# Sheet1.net
KiCad netlist of a schematic drawn in Altium Designer
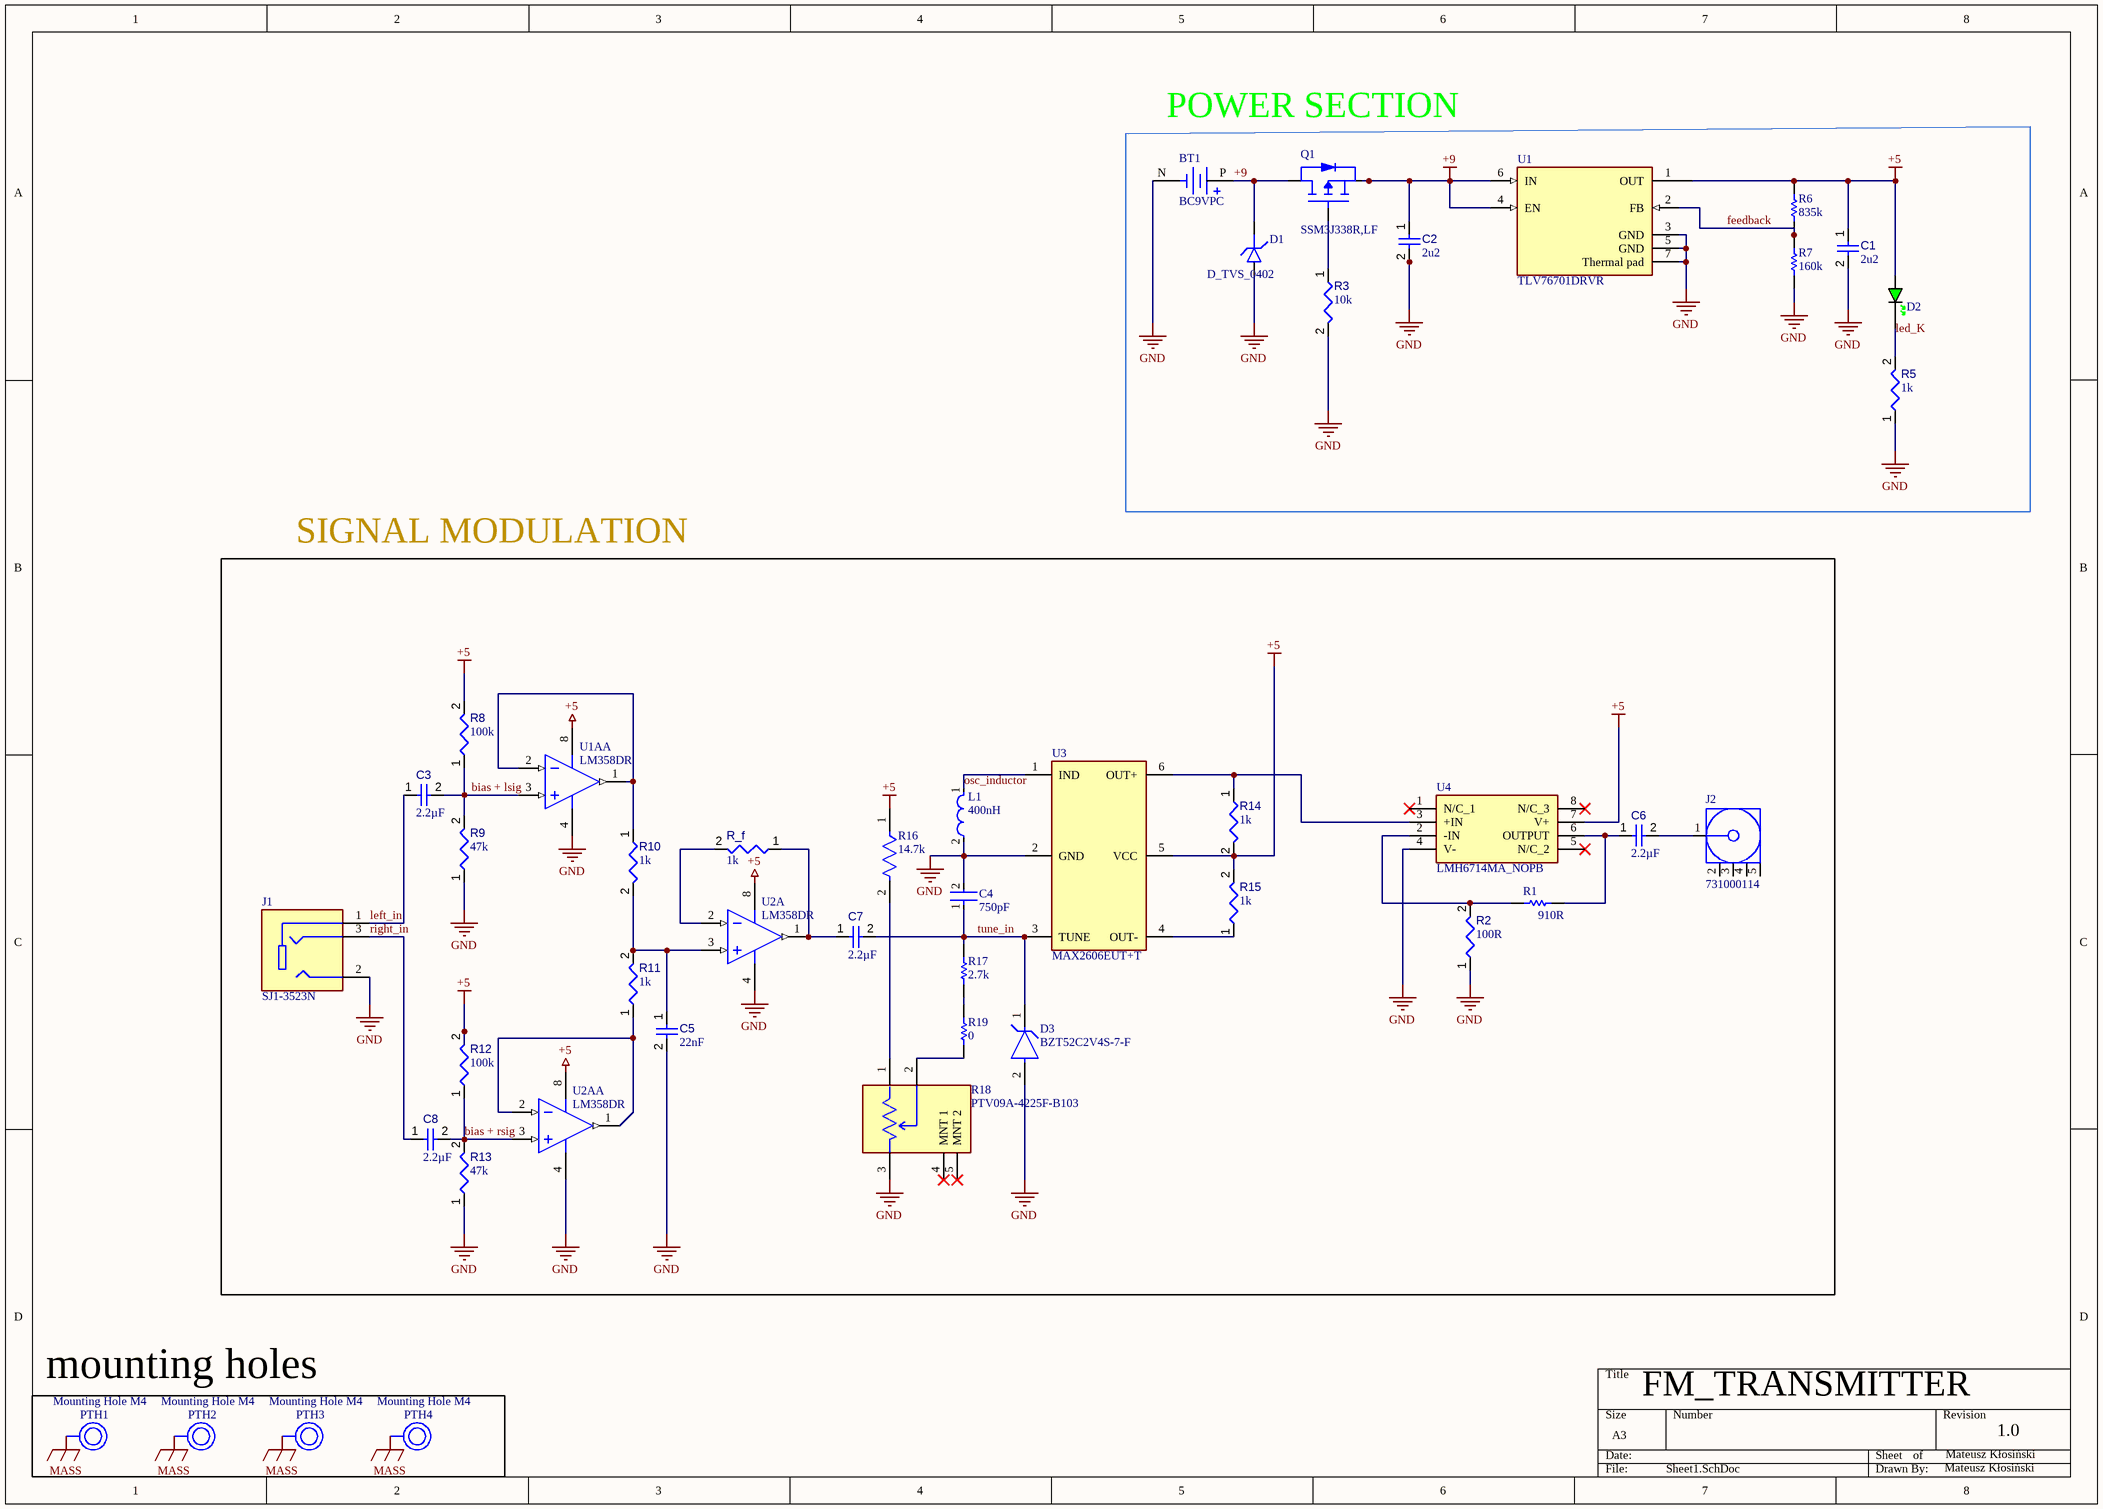
[diagram p0: Sheet1.SchDoc]

(export (version "E")
  (design (tool "Eeschema 10.0.6"))
  (components
    (comp (ref "BT1")
      (value "BC9VPC")
      (footprint "BAT_BC9VPC")
      (description "Battery Holder 1 Cells 9V Size Plastic Tray")
      (fields (field (name "MF") "MPD (Memory Protection Devices)"))
      (libsource (lib "PWr in Space team") (part "BC9VPC"))
    )
    (comp (ref "C1")
      (value "2u2")
      (footprint "CAPC0805(2012)145_L")
      (description "Chip Capacitor, 100µF +/-20%, 6.3V, 0805, Thickness 1.45 mm")
      (fields (field (name "TOLERANCE") "10%") (field (name "Comment") "Capacitor 100µF +/-20% 6.3V 0805"))
      (libsource (lib "PWr in Space team") (part "CAP-NP-2"))
    )
    (comp (ref "C2")
      (value "2u2")
      (footprint "CAPC0805(2012)145_L")
      (description "Chip Capacitor, 100µF +/-20%, 6.3V, 0805, Thickness 1.45 mm")
      (fields (field (name "TOLERANCE") "10%") (field (name "Comment") "Capacitor 100µF +/-20% 6.3V 0805"))
      (libsource (lib "PWr in Space team") (part "CAP-NP-2"))
    )
    (comp (ref "C3")
      (value "2.2µF")
      (footprint "CAPC0402(1005)60_L")
      (description "Chip Capacitor, 2,2µF +/-20%, 10V, 0402, Thickness 0.6 mm")
      (fields (field (name "TOLERANCE") "10%") (field (name "Comment") "Capacitor 2,2µF +/-20% 10V 0402"))
      (libsource (lib "PWr in Space team") (part "CAP-NP-2"))
    )
    (comp (ref "C4")
      (value "750pF")
      (footprint "FP-C0402-BB-MFG")
      (description "CAP CER 750PF 50V NP0 0402")
      (fields
        (field (name "MANUFACTURER") "Kemet")
        (field (name "OCTOPART") "https://octopart.com/c0402c751j5gactu-kemet-19049839")
      )
      (libsource (lib "Altium Content Vault") (part "b4654b650e69147ec39a6b967a45e02"))
    )
    (comp (ref "C5")
      (value "22nF")
      (footprint "CAPC0402(1005)60_L")
      (description "Chip Capacitor, 22nF +/-20%, 10V, 0402, Thickness 0.6 mm")
      (fields (field (name "TOLERANCE") "10%") (field (name "Comment") "Capacitor 22nF +/-20% 10V 0402"))
      (libsource (lib "PWr in Space team") (part "CAP-NP-2"))
    )
    (comp (ref "C6")
      (value "2.2µF")
      (footprint "CAPC0402(1005)60_L")
      (description "Chip Capacitor, 2,2µF +/-20%, 10V, 0402, Thickness 0.6 mm")
      (fields (field (name "TOLERANCE") "10%") (field (name "Comment") "Capacitor 2,2µF +/-20% 10V 0402"))
      (libsource (lib "PWr in Space team") (part "CAP-NP-2"))
    )
    (comp (ref "C7")
      (value "2.2µF")
      (footprint "CAPC0402(1005)60_L")
      (description "Chip Capacitor, 2,2µF +/-20%, 10V, 0402, Thickness 0.6 mm")
      (fields (field (name "TOLERANCE") "10%") (field (name "Comment") "Capacitor 2,2µF +/-20% 10V 0402"))
      (libsource (lib "PWr in Space team") (part "CAP-NP-2"))
    )
    (comp (ref "C8")
      (value "2.2µF")
      (footprint "CAPC0402(1005)60_L")
      (description "Chip Capacitor, 2,2µF +/-20%, 10V, 0402, Thickness 0.6 mm")
      (fields (field (name "TOLERANCE") "10%") (field (name "Comment") "Capacitor 2,2µF +/-20% 10V 0402"))
      (libsource (lib "PWr in Space team") (part "CAP-NP-2"))
    )
    (comp (ref "D1")
      (value "D_TVS_0402")
      (footprint "D_0402")
      (description "Diode TVS / ESD 0402")
      (libsource (lib "Schematic-Lib-PhilsLab") (part "D_TVS_0402"))
    )
    (comp (ref "D2")
      (value "GREEN")
      (footprint "LED_0805_GREEN")
      (description "LED 0805 GREEN SMD")
      (libsource (lib "Schematic-Lib-PhilsLab") (part "LED_0805_GREEN"))
    )
    (comp (ref "D3")
      (value "BZT52C2V4S-7-F")
      (footprint "FP-SOD323-IPC_B")
      (description "DIODE ZENER 2.4V 200MW SOD323")
      (fields (field (name "TOLERANCE") "8%"))
      (libsource (lib "Altium Content Vault") (part "f813f71cba58e380607f5dd3caf9714"))
    )
    (comp (ref "J1")
      (value "SJ1-3523N")
      (footprint "CUI_SJ1-3523N")
      (description "3.5 mm, Stereo, Right Angle, Through Hole, 3 Conductors, 0 Internal Switches, Audio Jack Connector")
      (fields (field (name "MF") "CUI Devices"))
      (libsource (lib "PWr in Space team") (part "SJ1-3523N"))
    )
    (comp (ref "J2")
      (value "731000114")
      (footprint "MOLX-731000114_V")
      (description "SMA Right-Angle PCB Jack Receptacle, Brass Body, Gold Plated, 50 Ohm, 5-Pin THD, RoHS, Tray")
      (fields (field (name "MANUFACTURER") "Molex"))
      (libsource (lib "Altium Content Vault") (part "CN-S-4F-RF5"))
    )
    (comp (ref "L1")
      (value "400nH")
      (footprint "FP-LQW18CA_00-MFG")
      (description "Wire Wound Ferrite type RF Inductor 400nH ±5% 680mA 0.26Ω 0603 (1608)")
      (libsource (lib "Altium Content Vault") (part "725321dda6339637d4d059423bc1c3c"))
    )
    (comp (ref "PTH1")
      (value "Mounting Hole M4")
      (footprint "Mounting Hole M4")
      (description "M4 size screw hole")
      (libsource (lib "PWr in Space team") (part "Mounting Hole M4"))
    )
    (comp (ref "PTH2")
      (value "Mounting Hole M4")
      (footprint "Mounting Hole M4")
      (description "M4 size screw hole")
      (libsource (lib "PWr in Space team") (part "Mounting Hole M4"))
    )
    (comp (ref "PTH3")
      (value "Mounting Hole M4")
      (footprint "Mounting Hole M4")
      (description "M4 size screw hole")
      (libsource (lib "PWr in Space team") (part "Mounting Hole M4"))
    )
    (comp (ref "PTH4")
      (value "Mounting Hole M4")
      (footprint "Mounting Hole M4")
      (description "M4 size screw hole")
      (libsource (lib "PWr in Space team") (part "Mounting Hole M4"))
    )
    (comp (ref "Q1")
      (value "SSM3J338R,LF")
      (footprint "SSM3J338R,LF-SOT23-F")
      (description "MOSFET P-Channel Vds=12V Id=6A")
      (fields (field (name "MANUFACTURER PART NUMBER") "Toshiba"))
      (libsource (lib "Schematic-Lib-PhilsLab") (part "SSM3J338R,LF"))
    )
    (comp (ref "R1")
      (value "910R")
      (footprint "RESC1608X55X30NL15T15")
      (fields (field (name "MANUFACTURER") "Panasonic") (field (name "PART NUMBER") "ERJ-3EKF9100V"))
      (libsource (lib "Altium Content Vault") (part "RES"))
    )
    (comp (ref "R2")
      (value "100R")
      (footprint "RESC0402(1005)_L")
      (description "100R 0.063W 1% 0402 (1005 Metric)  SMD")
      (fields (field (name "TOLERANCE") "1%") (field (name "POWER") "63mW"))
      (libsource (lib "PWr in Space team") (part "100R2F"))
    )
    (comp (ref "R3")
      (value "10k")
      (footprint "RESC0402(1005)_L")
      (description "10K 0.063W 1% 0402 (1005 Metric)  SMD")
      (fields (field (name "POWER") "63mW") (field (name "TOLERANCE") "1%"))
      (libsource (lib "PWr in Space team") (part "10KR2F"))
    )
    (comp (ref "R5")
      (value "1k")
      (footprint "RESC0805(2012)_L")
      (description "1K 0.125W 5% 0805 (2012 Metric)  SMD")
      (fields (field (name "TOLERANCE") "5%") (field (name "POWER") "125mW"))
      (libsource (lib "PWr in Space team") (part "1KR5J"))
    )
    (comp (ref "R6")
      (value "Resistor 1k +/-1% 0805 125 mW")
      (footprint "RESC2013X70X40ML20T20")
      (description "Chip Resistor, 1 KOhm, +/- 1%, 0.125 W, -55 to 155 degC, 0805 (2013 Metric)")
      (fields (field (name "TOLERANCE") "1%") (field (name "POWER") "125mW") (field (name "840K") "835k"))
      (libsource (lib "") (part "RES-2_1"))
    )
    (comp (ref "R7")
      (value "160k")
      (footprint "RESC2013X70X40ML20T20")
      (description "Chip Resistor, 1 KOhm, +/- 1%, 0.125 W, -55 to 155 degC, 0805 (2013 Metric)")
      (fields (field (name "TOLERANCE") "1%") (field (name "POWER") "125mW"))
      (libsource (lib "") (part "RES-2_1"))
    )
    (comp (ref "R8")
      (value "100k")
      (footprint "RESC1608X55X25ML10T15")
      (description "Chip Resistor, 100 KOhm, +/- 1%, 0.1 W, -55 to 155 degC, 0603 (1608 Metric)")
      (fields (field (name "TOLERANCE") "1%") (field (name "POWER") "100mW"))
      (libsource (lib "PWr in Space team") (part "RES-2"))
    )
    (comp (ref "R9")
      (value "47k")
      (footprint "FP-ERA2A-IPC_B")
      (description "Fixed Resistor, Thin Film, 0.063W, 47000ohm, 50V, 0.1% +/-Tol, 25ppm/Cel, Surface Mount, 0402")
      (fields (field (name "TOLERANCE") "0.1%") (field (name "POWER") "63mW"))
      (libsource (lib "PWr in Space team") (part "RES-2"))
    )
    (comp (ref "R10")
      (value "1k")
      (footprint "RESC0805(2012)_L")
      (description "1K 0.125W 5% 0805 (2012 Metric)  SMD")
      (fields (field (name "TOLERANCE") "5%") (field (name "POWER") "125mW"))
      (libsource (lib "PWr in Space team") (part "1KR5J"))
    )
    (comp (ref "R11")
      (value "1k")
      (footprint "RESC0805(2012)_L")
      (description "1K 0.125W 5% 0805 (2012 Metric)  SMD")
      (fields (field (name "TOLERANCE") "5%") (field (name "POWER") "125mW"))
      (libsource (lib "PWr in Space team") (part "1KR5J"))
    )
    (comp (ref "R12")
      (value "100k")
      (footprint "RESC1608X55X25ML10T15")
      (description "Chip Resistor, 100 KOhm, +/- 1%, 0.1 W, -55 to 155 degC, 0603 (1608 Metric)")
      (fields (field (name "TOLERANCE") "1%") (field (name "POWER") "100mW"))
      (libsource (lib "PWr in Space team") (part "RES-2"))
    )
    (comp (ref "R13")
      (value "47k")
      (footprint "FP-ERA2A-IPC_B")
      (description "Fixed Resistor, Thin Film, 0.063W, 47000ohm, 50V, 0.1% +/-Tol, 25ppm/Cel, Surface Mount, 0402")
      (fields (field (name "TOLERANCE") "0.1%") (field (name "POWER") "63mW"))
      (libsource (lib "PWr in Space team") (part "RES-2"))
    )
    (comp (ref "R14")
      (value "1k")
      (footprint "RESC0805(2012)_L")
      (description "1K 0.125W 5% 0805 (2012 Metric)  SMD")
      (fields (field (name "TOLERANCE") "5%") (field (name "POWER") "125mW"))
      (libsource (lib "PWr in Space team") (part "1KR5J"))
    )
    (comp (ref "R15")
      (value "1k")
      (footprint "RESC0805(2012)_L")
      (description "1K 0.125W 5% 0805 (2012 Metric)  SMD")
      (fields (field (name "TOLERANCE") "5%") (field (name "POWER") "125mW"))
      (libsource (lib "PWr in Space team") (part "1KR5J"))
    )
    (comp (ref "R16")
      (value "14.7k")
      (footprint "FP-ERA3A-MFG")
      (description "RES SMD 14.7KOHM 0.1% 1/10W 0603")
      (fields
        (field (name "OCTOPART") "https://octopart.com/era3aeb1472v-panasonic-42876006")
        (field (name "TOLERANCE") "0.1%")
      )
      (libsource (lib "Altium Content Vault") (part "1029c3af85768c4190bb7ad29bc67b5"))
    )
    (comp (ref "R17")
      (value "2.7k")
      (footprint "RESC1608X55X30NL20T20")
      (fields (field (name "MANUFACTURER") "Panasonic") (field (name "PART NUMBER") "ERA3AEB272V"))
      (libsource (lib "Altium Content Vault") (part "RES"))
    )
    (comp (ref "R18")
      (value "PTV09A-4225F-B103")
      (footprint "FP-PTV09A-4-MFG")
      (description "POT 10K OHM 1/20W CARBON LINEAR")
      (fields (field (name "TOLERANCE") "20%"))
      (libsource (lib "Altium Content Vault") (part "705d11b747745a787204d796a5f3d12"))
    )
    (comp (ref "R19")
      (value "0")
      (footprint "RESC1005X40X25ML05T10")
      (description "Chip Resistor, 0 Ohm, 0.063 W, -55 to 155 degC, 0402 (1005 Metric)")
      (fields (field (name "POWER") "63mW") (field (name "Comment") "Resistor 0R 0402 63 mW"))
      (libsource (lib "") (part "RES-2_1"))
    )
    (comp (ref "R_f")
      (value "1k")
      (footprint "RESC0805(2012)_L")
      (description "1K 0.125W 5% 0805 (2012 Metric)  SMD")
      (fields (field (name "TOLERANCE") "5%") (field (name "POWER") "125mW"))
      (libsource (lib "PWr in Space team") (part "1KR5J"))
    )
    (comp (ref "U1")
      (value "TLV76701DRVR")
      (footprint "FP-DRV0006A-IPC_C")
      (description "IC REG LINEAR POS ADJ 1A 6WSON")
      (libsource (lib "Altium Content Vault") (part "02b25d0a349586096ecc9dc1ae98da2"))
    )
    (comp (ref "U1A")
      (value "LM358DR")
      (footprint "D0008A_L")
      (fields (field (name "MANUFACTURER") "Texas Instruments (TI)"))
      (libsource (lib "PWr in Space team") (part "TI-LM358-8"))
    )
    (comp (ref "U2")
      (value "LM358DR")
      (footprint "D0008A_L")
      (fields (field (name "MANUFACTURER") "Texas Instruments (TI)"))
      (libsource (lib "PWr in Space team") (part "TI-LM358-8"))
    )
    (comp (ref "U2A")
      (value "LM358DR")
      (footprint "D0008A_L")
      (fields (field (name "MANUFACTURER") "Texas Instruments (TI)"))
      (libsource (lib "PWr in Space team") (part "TI-LM358-8"))
    )
    (comp (ref "U3")
      (value "MAX2606EUT+T")
      (footprint "SOT95P280X145-6N")
      (description "VCO Oscillators 45MHz to 650MHz, Integrated IF VCOs with Differential Output")
      (fields (field (name "MOUSER PART NUMBER") "700-MAX2606EUTT"))
      (libsource (lib "MAX2606EUT+T") (part "MAX2606EUT+T"))
    )
    (comp (ref "U4")
      (value "LMH6714MA_NOPB")
      (footprint "SOIC127P600X175-8N")
      (description "Video op amp,LMH6714MA 250MHz  SO8")
      (fields
        (field (name "MOUSER PART NUMBER") "926-LMH6714MA/NOPB")
        (field (name "MANUFACTURER_PART_NUMBER") "LMH6714MA/NOPB")
      )
      (libsource (lib "LMH6714MA_NOPB") (part "LMH6714MA_NOPB"))
    )
  )
  (nets
    (net (code "1") (name "+5") (class "Default")
      (node (ref "C1") (pin "1") (pinfunction "1_1") (pintype "passive"))
      (node (ref "D2") (pin "A") (pinfunction "A_A") (pintype "passive"))
      (node (ref "R12") (pin "2") (pinfunction "2_2") (pintype "passive"))
      (node (ref "R14") (pin "2") (pinfunction "2_2") (pintype "passive"))
      (node (ref "R15") (pin "2") (pinfunction "2_2") (pintype "passive"))
      (node (ref "R16") (pin "1") (pinfunction "1_1") (pintype "passive"))
      (node (ref "R6") (pin "2") (pinfunction "2_2") (pintype "passive"))
      (node (ref "R8") (pin "2") (pinfunction "2_2") (pintype "passive"))
      (node (ref "U1") (pin "1") (pinfunction "OUT_1") (pintype "passive"))
      (node (ref "U1A") (pin "8") (pinfunction "VCC_8") (pintype "power_in"))
      (node (ref "U2") (pin "8") (pinfunction "VCC_8") (pintype "power_in"))
      (node (ref "U2A") (pin "8") (pinfunction "VCC_8") (pintype "power_in"))
      (node (ref "U3") (pin "5") (pinfunction "VCC_5") (pintype "passive"))
      (node (ref "U4") (pin "7") (pinfunction "V+_7") (pintype "passive"))
    )
    (net (code "2") (name "+9") (class "Default")
      (node (ref "BT1") (pin "P") (pinfunction "POS_P") (pintype "passive"))
      (node (ref "C2") (pin "1") (pinfunction "1_1") (pintype "passive"))
      (node (ref "D1") (pin "K") (pinfunction "K_K") (pintype "passive"))
      (node (ref "Q1") (pin "D") (pinfunction "D_D") (pintype "passive"))
      (node (ref "Q1") (pin "S") (pinfunction "S_S") (pintype "passive"))
      (node (ref "U1") (pin "4") (pinfunction "EN_4") (pintype "input"))
      (node (ref "U1") (pin "6") (pinfunction "IN_6") (pintype "input"))
    )
    (net (code "3") (name "/bias + lsig") (class "Default")
      (node (ref "C3") (pin "2") (pinfunction "2_2") (pintype "passive"))
      (node (ref "R8") (pin "1") (pinfunction "1_1") (pintype "passive"))
      (node (ref "R9") (pin "2") (pinfunction "2_2") (pintype "passive"))
      (node (ref "U1A") (pin "3") (pinfunction "1IN+_3") (pintype "input"))
    )
    (net (code "4") (name "/bias + rsig") (class "Default")
      (node (ref "C8") (pin "2") (pinfunction "2_2") (pintype "passive"))
      (node (ref "R12") (pin "1") (pinfunction "1_1") (pintype "passive"))
      (node (ref "R13") (pin "2") (pinfunction "2_2") (pintype "passive"))
      (node (ref "U2A") (pin "3") (pinfunction "1IN+_3") (pintype "input"))
    )
    (net (code "5") (name "/feedback") (class "Default")
      (node (ref "R6") (pin "1") (pinfunction "1_1") (pintype "passive"))
      (node (ref "R7") (pin "2") (pinfunction "2_2") (pintype "passive"))
      (node (ref "U1") (pin "2") (pinfunction "FB_2") (pintype "input"))
    )
    (net (code "6") (name "/led_K") (class "Default")
      (node (ref "D2") (pin "K") (pinfunction "K_K") (pintype "passive"))
      (node (ref "R5") (pin "2") (pinfunction "2_2") (pintype "passive"))
    )
    (net (code "7") (name "/left_in") (class "Default")
      (node (ref "C3") (pin "1") (pinfunction "1_1") (pintype "passive"))
      (node (ref "J1") (pin "1") (pinfunction "1_1") (pintype "passive"))
    )
    (net (code "8") (name "/osc_inductor") (class "Default")
      (node (ref "L1") (pin "1") (pinfunction "1_1") (pintype "passive"))
      (node (ref "U3") (pin "1") (pinfunction "IND_1") (pintype "passive"))
    )
    (net (code "9") (name "/right_in") (class "Default")
      (node (ref "C8") (pin "1") (pinfunction "1_1") (pintype "passive"))
      (node (ref "J1") (pin "3") (pinfunction "3_3") (pintype "passive"))
    )
    (net (code "10") (name "/tune_in") (class "Default")
      (node (ref "C4") (pin "1") (pinfunction "1_1") (pintype "passive"))
      (node (ref "C7") (pin "2") (pinfunction "2_2") (pintype "passive"))
      (node (ref "D3") (pin "1") (pinfunction "C_1") (pintype "passive"))
      (node (ref "R17") (pin "2") (pinfunction "2_2") (pintype "passive"))
      (node (ref "U3") (pin "3") (pinfunction "TUNE_3") (pintype "passive"))
    )
    (net (code "11") (name "GND") (class "Default")
      (node (ref "BT1") (pin "N") (pinfunction "NEG_N") (pintype "passive"))
      (node (ref "C1") (pin "2") (pinfunction "2_2") (pintype "passive"))
      (node (ref "C2") (pin "2") (pinfunction "2_2") (pintype "passive"))
      (node (ref "C4") (pin "2") (pinfunction "2_2") (pintype "passive"))
      (node (ref "C5") (pin "2") (pinfunction "2_2") (pintype "passive"))
      (node (ref "D1") (pin "A") (pinfunction "A_A") (pintype "passive"))
      (node (ref "D3") (pin "2") (pinfunction "A_2") (pintype "passive"))
      (node (ref "J1") (pin "2") (pinfunction "2_2") (pintype "passive"))
      (node (ref "L1") (pin "2") (pinfunction "2_2") (pintype "passive"))
      (node (ref "R13") (pin "1") (pinfunction "1_1") (pintype "passive"))
      (node (ref "R18") (pin "3") (pinfunction "3_3") (pintype "passive"))
      (node (ref "R2") (pin "1") (pinfunction "1_1") (pintype "passive"))
      (node (ref "R3") (pin "2") (pinfunction "2_2") (pintype "passive"))
      (node (ref "R5") (pin "1") (pinfunction "1_1") (pintype "passive"))
      (node (ref "R7") (pin "1") (pinfunction "1_1") (pintype "passive"))
      (node (ref "R9") (pin "1") (pinfunction "1_1") (pintype "passive"))
      (node (ref "U1") (pin "3") (pinfunction "GND_3") (pintype "power_in"))
      (node (ref "U1") (pin "5") (pinfunction "GND_5") (pintype "power_in"))
      (node (ref "U1") (pin "7") (pinfunction "Thermal_pad_7") (pintype "power_in"))
      (node (ref "U1A") (pin "4") (pinfunction "GND_4") (pintype "power_in"))
      (node (ref "U2") (pin "4") (pinfunction "GND_4") (pintype "power_in"))
      (node (ref "U2A") (pin "4") (pinfunction "GND_4") (pintype "power_in"))
      (node (ref "U3") (pin "2") (pinfunction "GND_2") (pintype "passive"))
      (node (ref "U4") (pin "4") (pinfunction "V-_4") (pintype "passive"))
    )
    (net (code "12") (name "MASS") (class "Default")
      (node (ref "PTH1") (pin "3") (pinfunction "3_3") (pintype "passive"))
      (node (ref "PTH2") (pin "3") (pinfunction "3_3") (pintype "passive"))
      (node (ref "PTH3") (pin "3") (pinfunction "3_3") (pintype "passive"))
      (node (ref "PTH4") (pin "3") (pinfunction "3_3") (pintype "passive"))
    )
    (net (code "13") (name "Net-(C6-Pad2)") (class "Default")
      (node (ref "C6") (pin "2") (pinfunction "2_2") (pintype "passive"))
      (node (ref "J2") (pin "1") (pinfunction "1_1") (pintype "passive"))
    )
    (net (code "14") (name "Net-(Q1-PadG)") (class "Default")
      (node (ref "Q1") (pin "G") (pinfunction "G_G") (pintype "passive"))
      (node (ref "R3") (pin "1") (pinfunction "1_1") (pintype "passive"))
    )
    (net (code "15") (name "Net-(R16-Pad2)") (class "Default")
      (node (ref "R16") (pin "2") (pinfunction "2_2") (pintype "passive"))
      (node (ref "R18") (pin "1") (pinfunction "1_1") (pintype "passive"))
    )
    (net (code "16") (name "Net-(R17-Pad1)") (class "Default")
      (node (ref "R17") (pin "1") (pinfunction "1_1") (pintype "passive"))
      (node (ref "R19") (pin "2") (pinfunction "2_2") (pintype "passive"))
    )
    (net (code "17") (name "Net-(R18-Pad2)") (class "Default")
      (node (ref "R18") (pin "2") (pinfunction "2_2") (pintype "passive"))
      (node (ref "R19") (pin "1") (pinfunction "1_1") (pintype "passive"))
    )
    (net (code "18") (name "Net-(U1AA-1IN-)") (class "Default")
      (node (ref "R10") (pin "1") (pinfunction "1_1") (pintype "passive"))
      (node (ref "U1A") (pin "1") (pinfunction "1OUT_1") (pintype "output"))
      (node (ref "U1A") (pin "2") (pinfunction "1IN-_2") (pintype "input"))
    )
    (net (code "19") (name "Net-(U2A-1IN+)") (class "Default")
      (node (ref "C5") (pin "1") (pinfunction "1_1") (pintype "passive"))
      (node (ref "R10") (pin "2") (pinfunction "2_2") (pintype "passive"))
      (node (ref "R11") (pin "2") (pinfunction "2_2") (pintype "passive"))
      (node (ref "U2") (pin "3") (pinfunction "1IN+_3") (pintype "input"))
    )
    (net (code "20") (name "Net-(U2A-1IN-)") (class "Default")
      (node (ref "R_f") (pin "2") (pinfunction "2_2") (pintype "passive"))
      (node (ref "U2") (pin "2") (pinfunction "1IN-_2") (pintype "input"))
    )
    (net (code "21") (name "Net-(U2A-1OUT)") (class "Default")
      (node (ref "C7") (pin "1") (pinfunction "1_1") (pintype "passive"))
      (node (ref "R_f") (pin "1") (pinfunction "1_1") (pintype "passive"))
      (node (ref "U2") (pin "1") (pinfunction "1OUT_1") (pintype "output"))
    )
    (net (code "22") (name "Net-(U2AA-1IN-)") (class "Default")
      (node (ref "R11") (pin "1") (pinfunction "1_1") (pintype "passive"))
      (node (ref "U2A") (pin "1") (pinfunction "1OUT_1") (pintype "output"))
      (node (ref "U2A") (pin "2") (pinfunction "1IN-_2") (pintype "input"))
    )
    (net (code "23") (name "Net-(U3-OUT+)") (class "Default")
      (node (ref "R14") (pin "1") (pinfunction "1_1") (pintype "passive"))
      (node (ref "U3") (pin "6") (pinfunction "OUT+_6") (pintype "passive"))
      (node (ref "U4") (pin "3") (pinfunction "+IN_3") (pintype "passive"))
    )
    (net (code "24") (name "Net-(U3-OUT-)") (class "Default")
      (node (ref "R15") (pin "1") (pinfunction "1_1") (pintype "passive"))
      (node (ref "U3") (pin "4") (pinfunction "OUT-_4") (pintype "passive"))
    )
    (net (code "25") (name "Net-(U4--IN)") (class "Default")
      (node (ref "R1") (pin "1") (pinfunction "1_1") (pintype "passive"))
      (node (ref "R2") (pin "2") (pinfunction "2_2") (pintype "passive"))
      (node (ref "U4") (pin "2") (pinfunction "-IN_2") (pintype "passive"))
    )
    (net (code "26") (name "Net-(U4-OUTPUT)") (class "Default")
      (node (ref "C6") (pin "1") (pinfunction "1_1") (pintype "passive"))
      (node (ref "R1") (pin "2") (pinfunction "2_2") (pintype "passive"))
      (node (ref "U4") (pin "6") (pinfunction "OUTPUT_6") (pintype "passive"))
    )
    (net (code "27") (name "unconnected-(J2-Pad2)") (class "Default")
      (node (ref "J2") (pin "2") (pinfunction "2_2") (pintype "passive"))
    )
    (net (code "28") (name "unconnected-(J2-Pad3)") (class "Default")
      (node (ref "J2") (pin "3") (pinfunction "3_3") (pintype "passive"))
    )
    (net (code "29") (name "unconnected-(J2-Pad4)") (class "Default")
      (node (ref "J2") (pin "4") (pinfunction "4_4") (pintype "passive"))
    )
    (net (code "30") (name "unconnected-(J2-Pad5)") (class "Default")
      (node (ref "J2") (pin "5") (pinfunction "5_5") (pintype "passive"))
    )
    (net (code "31") (name "unconnected-(R18-MNT_1-Pad4)") (class "Default")
      (node (ref "R18") (pin "4") (pinfunction "MNT_1_4") (pintype "passive+no_connect"))
    )
    (net (code "32") (name "unconnected-(R18-MNT_2-Pad5)") (class "Default")
      (node (ref "R18") (pin "5") (pinfunction "MNT_2_5") (pintype "passive+no_connect"))
    )
    (net (code "33") (name "unconnected-(U4-N{slash}C_1-Pad1)") (class "Default")
      (node (ref "U4") (pin "1") (pinfunction "N/C_1_1") (pintype "passive+no_connect"))
    )
    (net (code "34") (name "unconnected-(U4-N{slash}C_2-Pad5)") (class "Default")
      (node (ref "U4") (pin "5") (pinfunction "N/C_2_5") (pintype "passive+no_connect"))
    )
    (net (code "35") (name "unconnected-(U4-N{slash}C_3-Pad8)") (class "Default")
      (node (ref "U4") (pin "8") (pinfunction "N/C_3_8") (pintype "passive+no_connect"))
    )
  )
)
